# Board_Connect.net
KiCad netlist of a schematic drawn in Altium Designer
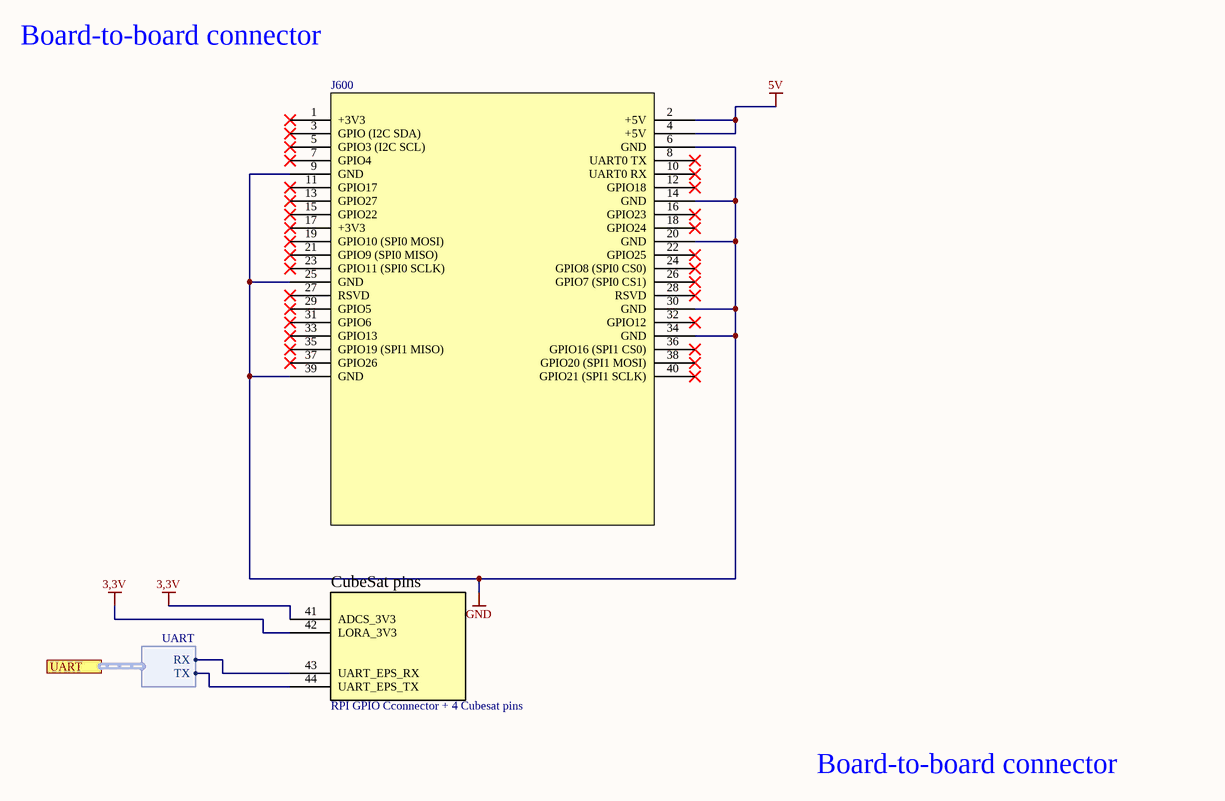
[diagram p0: Board_Connect.SchDoc]

(export (version "E")
  (design (tool "Eeschema 10.0.6"))
  (components
    (comp (ref "J600")
      (value "RPI GPIO Cconnector + 4 Cubesat pins")
      (footprint "RPI GPIO")
      (libsource (lib "SCHEMATIC") (part "Connector GPIO"))
    )
  )
  (nets
    (net (code "2") (name "/RX") (class "Default")
      (node (ref "J600") (pin "43") (pinfunction "UART_EPS_RX_43") (pintype "passive"))
    )
    (net (code "3") (name "/TX") (class "Default")
      (node (ref "J600") (pin "44") (pinfunction "UART_EPS_TX_44") (pintype "passive"))
    )
    (net (code "5") (name "3,3V") (class "Default")
      (node (ref "J600") (pin "41") (pinfunction "ADCS_3V3_41") (pintype "passive"))
      (node (ref "J600") (pin "42") (pinfunction "LORA_3V3_42") (pintype "passive"))
    )
    (net (code "6") (name "5V") (class "Default")
      (node (ref "J600") (pin "2") (pinfunction "+5V_2") (pintype "passive"))
      (node (ref "J600") (pin "4") (pinfunction "+5V_4") (pintype "passive"))
    )
    (net (code "7") (name "GND") (class "Default")
      (node (ref "J600") (pin "14") (pinfunction "GND_14") (pintype "passive"))
      (node (ref "J600") (pin "20") (pinfunction "GND_20") (pintype "passive"))
      (node (ref "J600") (pin "25") (pinfunction "GND_25") (pintype "passive"))
      (node (ref "J600") (pin "30") (pinfunction "GND_30") (pintype "passive"))
      (node (ref "J600") (pin "34") (pinfunction "GND_34") (pintype "passive"))
      (node (ref "J600") (pin "39") (pinfunction "GND_39") (pintype "passive"))
      (node (ref "J600") (pin "6") (pinfunction "GND_6") (pintype "passive"))
      (node (ref "J600") (pin "9") (pinfunction "GND_9") (pintype "passive"))
    )
    (net (code "8") (name "unconnected-(J600-+3V3-Pad1)") (class "Default")
      (node (ref "J600") (pin "1") (pinfunction "+3V3_1") (pintype "passive+no_connect"))
    )
    (net (code "9") (name "unconnected-(J600-+3V3-Pad17)") (class "Default")
      (node (ref "J600") (pin "17") (pinfunction "+3V3_17") (pintype "passive+no_connect"))
    )
    (net (code "10") (name "unconnected-(J600-GPIO3_(I2C_SCL)-Pad5)") (class "Default")
      (node (ref "J600") (pin "5") (pinfunction "GPIO3_(I2C_SCL)_5") (pintype "passive+no_connect"))
    )
    (net (code "11") (name "unconnected-(J600-GPIO4-Pad7)") (class "Default")
      (node (ref "J600") (pin "7") (pinfunction "GPIO4_7") (pintype "passive+no_connect"))
    )
    (net (code "12") (name "unconnected-(J600-GPIO5-Pad29)") (class "Default")
      (node (ref "J600") (pin "29") (pinfunction "GPIO5_29") (pintype "passive+no_connect"))
    )
    (net (code "13") (name "unconnected-(J600-GPIO6-Pad31)") (class "Default")
      (node (ref "J600") (pin "31") (pinfunction "GPIO6_31") (pintype "passive+no_connect"))
    )
    (net (code "14") (name "unconnected-(J600-GPIO7_(SPI0_CS1)-Pad26)") (class "Default")
      (node (ref "J600") (pin "26") (pinfunction "GPIO7_(SPI0_CS1)_26") (pintype "passive+no_connect"))
    )
    (net (code "15") (name "unconnected-(J600-GPIO8_(SPI0_CS0)-Pad24)") (class "Default")
      (node (ref "J600") (pin "24") (pinfunction "GPIO8_(SPI0_CS0)_24") (pintype "passive+no_connect"))
    )
    (net (code "16") (name "unconnected-(J600-GPIO9_(SPI0_MISO)-Pad21)") (class "Default")
      (node (ref "J600") (pin "21") (pinfunction "GPIO9_(SPI0_MISO)_21") (pintype "passive+no_connect"))
    )
    (net (code "17") (name "unconnected-(J600-GPIO10_(SPI0_MOSI)-Pad19)") (class "Default")
      (node (ref "J600") (pin "19") (pinfunction "GPIO10_(SPI0_MOSI)_19") (pintype "passive+no_connect"))
    )
    (net (code "18") (name "unconnected-(J600-GPIO11_(SPI0_SCLK)-Pad23)") (class "Default")
      (node (ref "J600") (pin "23") (pinfunction "GPIO11_(SPI0_SCLK)_23") (pintype "passive+no_connect"))
    )
    (net (code "19") (name "unconnected-(J600-GPIO12-Pad32)") (class "Default")
      (node (ref "J600") (pin "32") (pinfunction "GPIO12_32") (pintype "passive+no_connect"))
    )
    (net (code "20") (name "unconnected-(J600-GPIO13-Pad33)") (class "Default")
      (node (ref "J600") (pin "33") (pinfunction "GPIO13_33") (pintype "passive+no_connect"))
    )
    (net (code "21") (name "unconnected-(J600-GPIO16_(SPI1_CS0)-Pad36)") (class "Default")
      (node (ref "J600") (pin "36") (pinfunction "GPIO16_(SPI1_CS0)_36") (pintype "passive+no_connect"))
    )
    (net (code "22") (name "unconnected-(J600-GPIO17-Pad11)") (class "Default")
      (node (ref "J600") (pin "11") (pinfunction "GPIO17_11") (pintype "passive+no_connect"))
    )
    (net (code "23") (name "unconnected-(J600-GPIO18-Pad12)") (class "Default")
      (node (ref "J600") (pin "12") (pinfunction "GPIO18_12") (pintype "passive+no_connect"))
    )
    (net (code "24") (name "unconnected-(J600-GPIO19_(SPI1_MISO)-Pad35)") (class "Default")
      (node (ref "J600") (pin "35") (pinfunction "GPIO19_(SPI1_MISO)_35") (pintype "passive+no_connect"))
    )
    (net (code "25") (name "unconnected-(J600-GPIO20_(SPI1_MOSI)-Pad38)") (class "Default")
      (node (ref "J600") (pin "38") (pinfunction "GPIO20_(SPI1_MOSI)_38") (pintype "passive+no_connect"))
    )
    (net (code "26") (name "unconnected-(J600-GPIO21_(SPI1_SCLK)-Pad40)") (class "Default")
      (node (ref "J600") (pin "40") (pinfunction "GPIO21_(SPI1_SCLK)_40") (pintype "passive+no_connect"))
    )
    (net (code "27") (name "unconnected-(J600-GPIO22-Pad15)") (class "Default")
      (node (ref "J600") (pin "15") (pinfunction "GPIO22_15") (pintype "passive+no_connect"))
    )
    (net (code "28") (name "unconnected-(J600-GPIO23-Pad16)") (class "Default")
      (node (ref "J600") (pin "16") (pinfunction "GPIO23_16") (pintype "passive+no_connect"))
    )
    (net (code "29") (name "unconnected-(J600-GPIO24-Pad18)") (class "Default")
      (node (ref "J600") (pin "18") (pinfunction "GPIO24_18") (pintype "passive+no_connect"))
    )
    (net (code "30") (name "unconnected-(J600-GPIO25-Pad22)") (class "Default")
      (node (ref "J600") (pin "22") (pinfunction "GPIO25_22") (pintype "passive+no_connect"))
    )
    (net (code "31") (name "unconnected-(J600-GPIO26-Pad37)") (class "Default")
      (node (ref "J600") (pin "37") (pinfunction "GPIO26_37") (pintype "passive+no_connect"))
    )
    (net (code "32") (name "unconnected-(J600-GPIO27-Pad13)") (class "Default")
      (node (ref "J600") (pin "13") (pinfunction "GPIO27_13") (pintype "passive+no_connect"))
    )
    (net (code "33") (name "unconnected-(J600-GPIO_(I2C_SDA)-Pad3)") (class "Default")
      (node (ref "J600") (pin "3") (pinfunction "GPIO_(I2C_SDA)_3") (pintype "passive+no_connect"))
    )
    (net (code "34") (name "unconnected-(J600-RSVD-Pad27)") (class "Default")
      (node (ref "J600") (pin "27") (pinfunction "RSVD_27") (pintype "passive+no_connect"))
    )
    (net (code "35") (name "unconnected-(J600-RSVD-Pad28)") (class "Default")
      (node (ref "J600") (pin "28") (pinfunction "RSVD_28") (pintype "passive+no_connect"))
    )
    (net (code "36") (name "unconnected-(J600-UART0_RX-Pad10)") (class "Default")
      (node (ref "J600") (pin "10") (pinfunction "UART0_RX_10") (pintype "passive+no_connect"))
    )
    (net (code "37") (name "unconnected-(J600-UART0_TX-Pad8)") (class "Default")
      (node (ref "J600") (pin "8") (pinfunction "UART0_TX_8") (pintype "passive+no_connect"))
    )
  )
)
